# ESP32-S3-M_2_2024-03-15.net
KiCad netlist of a schematic drawn in Altium Designer
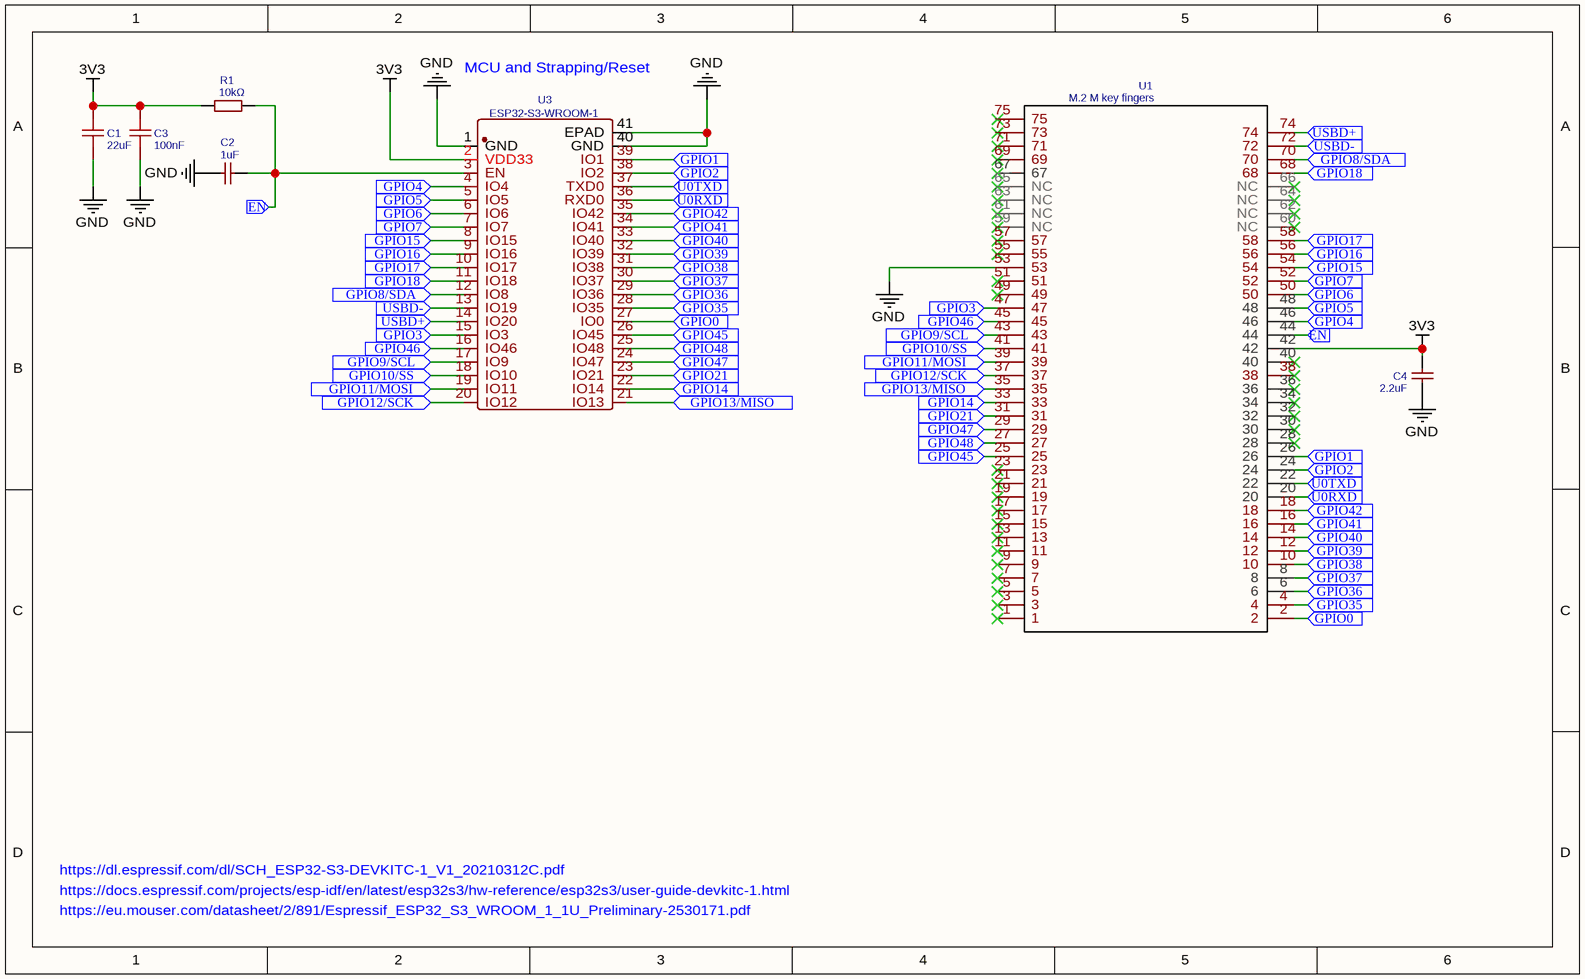
[diagram p0: ESP32-S3-M.2_2024-03-15.schdoc]

(export (version "E")
  (design (tool "Eeschema 10.0.6"))
  (components
    (comp (ref "C1")
      (value "22uF")
      (fields
        (field (name "MANUFACTURER") "SAMSUNG(三星)")
        (field (name "MANUFACTURER PART") "CL10A226MQ8NRNC")
      )
      (libsource (lib "altium-import") (part "root_1_22uF_"))
    )
    (comp (ref "C2")
      (value "1uF")
      (fields
        (field (name "MANUFACTURER PART") "CL10A105KB8NNNC")
        (field (name "MANUFACTURER") "SAMSUNG(三星)")
      )
      (libsource (lib "altium-import") (part "root_0_1uF_"))
    )
    (comp (ref "C3")
      (value "100nF")
      (fields
        (field (name "MANUFACTURER") "YAGEO(国巨)")
        (field (name "MANUFACTURER PART") "CC0603KRX7R9BB104")
      )
      (libsource (lib "altium-import") (part "root_1_100nF_"))
    )
    (comp (ref "C4")
      (value "2.2uF")
      (fields
        (field (name "MANUFACTURER PART") "CL10A225KP8NNNC")
        (field (name "MANUFACTURER") "SAMSUNG(三星)")
      )
      (libsource (lib "altium-import") (part "root_1_2.2uF_"))
    )
    (comp (ref "R1")
      (value "10kΩ")
      (fields (field (name "MANUFACTURER") "YAGEO(国巨)") (field (name "MANUFACTURER PART") "RC0603FR-0710KL"))
      (libsource (lib "altium-import") (part "root_0_10kΩ_"))
    )
    (comp (ref "U1")
      (value "M.2 M key fingers")
      (fields (field (name "CONTRIBUTOR") "Nikola Pantelin"))
      (libsource (lib "altium-import") (part "root_0_M.2 M key fingers_"))
    )
    (comp (ref "U3")
      (value "ESP32-S3-WROOM-1")
      (fields (field (name "MANUFACTURER") "Espressif Systems") (field (name "CONTRIBUTOR") "max30012540"))
      (libsource (lib "altium-import") (part "root_0_ESP32-S3-WROOM-1_"))
    )
  )
  (nets
    (net (code "1") (name "/EN") (class "Default")
      (node (ref "C2") (pin "2") (pinfunction "2_2") (pintype "passive"))
      (node (ref "R1") (pin "2") (pinfunction "2_2") (pintype "passive"))
      (node (ref "U1") (pin "44") (pinfunction "44_44") (pintype "passive"))
      (node (ref "U3") (pin "3") (pinfunction "EN_3") (pintype "passive"))
    )
    (net (code "2") (name "/GPIO0") (class "Default")
      (node (ref "U1") (pin "2") (pinfunction "2_2") (pintype "passive"))
      (node (ref "U3") (pin "27") (pinfunction "IO0_27") (pintype "passive"))
    )
    (net (code "3") (name "/GPIO1") (class "Default")
      (node (ref "U1") (pin "26") (pinfunction "26_26") (pintype "passive"))
      (node (ref "U3") (pin "39") (pinfunction "IO1_39") (pintype "passive"))
    )
    (net (code "4") (name "/GPIO2") (class "Default")
      (node (ref "U1") (pin "24") (pinfunction "24_24") (pintype "passive"))
      (node (ref "U3") (pin "38") (pinfunction "IO2_38") (pintype "passive"))
    )
    (net (code "5") (name "/GPIO3") (class "Default")
      (node (ref "U1") (pin "47") (pinfunction "47_47") (pintype "passive"))
      (node (ref "U3") (pin "15") (pinfunction "IO3_15") (pintype "passive"))
    )
    (net (code "6") (name "/GPIO4") (class "Default")
      (node (ref "U1") (pin "46") (pinfunction "46_46") (pintype "passive"))
      (node (ref "U3") (pin "4") (pinfunction "IO4_4") (pintype "passive"))
    )
    (net (code "7") (name "/GPIO5") (class "Default")
      (node (ref "U1") (pin "48") (pinfunction "48_48") (pintype "passive"))
      (node (ref "U3") (pin "5") (pinfunction "IO5_5") (pintype "passive"))
    )
    (net (code "8") (name "/GPIO6") (class "Default")
      (node (ref "U1") (pin "50") (pinfunction "50_50") (pintype "passive"))
      (node (ref "U3") (pin "6") (pinfunction "IO6_6") (pintype "passive"))
    )
    (net (code "9") (name "/GPIO7") (class "Default")
      (node (ref "U1") (pin "52") (pinfunction "52_52") (pintype "passive"))
      (node (ref "U3") (pin "7") (pinfunction "IO7_7") (pintype "passive"))
    )
    (net (code "10") (name "/GPIO8{slash}SDA") (class "Default")
      (node (ref "U1") (pin "70") (pinfunction "70_70") (pintype "passive"))
      (node (ref "U3") (pin "12") (pinfunction "IO8_12") (pintype "passive"))
    )
    (net (code "11") (name "/GPIO9{slash}SCL") (class "Default")
      (node (ref "U1") (pin "43") (pinfunction "43_43") (pintype "passive"))
      (node (ref "U3") (pin "17") (pinfunction "IO9_17") (pintype "passive"))
    )
    (net (code "12") (name "/GPIO10{slash}SS") (class "Default")
      (node (ref "U1") (pin "41") (pinfunction "41_41") (pintype "passive"))
      (node (ref "U3") (pin "18") (pinfunction "IO10_18") (pintype "passive"))
    )
    (net (code "13") (name "/GPIO11{slash}MOSI") (class "Default")
      (node (ref "U1") (pin "39") (pinfunction "39_39") (pintype "passive"))
      (node (ref "U3") (pin "19") (pinfunction "IO11_19") (pintype "passive"))
    )
    (net (code "14") (name "/GPIO12{slash}SCK") (class "Default")
      (node (ref "U1") (pin "37") (pinfunction "37_37") (pintype "passive"))
      (node (ref "U3") (pin "20") (pinfunction "IO12_20") (pintype "passive"))
    )
    (net (code "15") (name "/GPIO13{slash}MISO") (class "Default")
      (node (ref "U1") (pin "35") (pinfunction "35_35") (pintype "passive"))
      (node (ref "U3") (pin "21") (pinfunction "IO13_21") (pintype "passive"))
    )
    (net (code "16") (name "/GPIO14") (class "Default")
      (node (ref "U1") (pin "33") (pinfunction "33_33") (pintype "passive"))
      (node (ref "U3") (pin "22") (pinfunction "IO14_22") (pintype "passive"))
    )
    (net (code "17") (name "/GPIO15") (class "Default")
      (node (ref "U1") (pin "54") (pinfunction "54_54") (pintype "passive"))
      (node (ref "U3") (pin "8") (pinfunction "IO15_8") (pintype "passive"))
    )
    (net (code "18") (name "/GPIO16") (class "Default")
      (node (ref "U1") (pin "56") (pinfunction "56_56") (pintype "passive"))
      (node (ref "U3") (pin "9") (pinfunction "IO16_9") (pintype "passive"))
    )
    (net (code "19") (name "/GPIO17") (class "Default")
      (node (ref "U1") (pin "58") (pinfunction "58_58") (pintype "passive"))
      (node (ref "U3") (pin "10") (pinfunction "IO17_10") (pintype "passive"))
    )
    (net (code "20") (name "/GPIO18") (class "Default")
      (node (ref "U1") (pin "68") (pinfunction "68_68") (pintype "passive"))
      (node (ref "U3") (pin "11") (pinfunction "IO18_11") (pintype "passive"))
    )
    (net (code "21") (name "/GPIO21") (class "Default")
      (node (ref "U1") (pin "31") (pinfunction "31_31") (pintype "passive"))
      (node (ref "U3") (pin "23") (pinfunction "IO21_23") (pintype "passive"))
    )
    (net (code "22") (name "/GPIO35") (class "Default")
      (node (ref "U1") (pin "4") (pinfunction "4_4") (pintype "passive"))
      (node (ref "U3") (pin "28") (pinfunction "IO35_28") (pintype "passive"))
    )
    (net (code "23") (name "/GPIO36") (class "Default")
      (node (ref "U1") (pin "6") (pinfunction "6_6") (pintype "passive"))
      (node (ref "U3") (pin "29") (pinfunction "IO36_29") (pintype "passive"))
    )
    (net (code "24") (name "/GPIO37") (class "Default")
      (node (ref "U1") (pin "8") (pinfunction "8_8") (pintype "passive"))
      (node (ref "U3") (pin "30") (pinfunction "IO37_30") (pintype "passive"))
    )
    (net (code "25") (name "/GPIO38") (class "Default")
      (node (ref "U1") (pin "10") (pinfunction "10_10") (pintype "passive"))
      (node (ref "U3") (pin "31") (pinfunction "IO38_31") (pintype "passive"))
    )
    (net (code "26") (name "/GPIO39") (class "Default")
      (node (ref "U1") (pin "12") (pinfunction "12_12") (pintype "passive"))
      (node (ref "U3") (pin "32") (pinfunction "IO39_32") (pintype "passive"))
    )
    (net (code "27") (name "/GPIO40") (class "Default")
      (node (ref "U1") (pin "14") (pinfunction "14_14") (pintype "passive"))
      (node (ref "U3") (pin "33") (pinfunction "IO40_33") (pintype "passive"))
    )
    (net (code "28") (name "/GPIO41") (class "Default")
      (node (ref "U1") (pin "16") (pinfunction "16_16") (pintype "passive"))
      (node (ref "U3") (pin "34") (pinfunction "IO41_34") (pintype "passive"))
    )
    (net (code "29") (name "/GPIO42") (class "Default")
      (node (ref "U1") (pin "18") (pinfunction "18_18") (pintype "passive"))
      (node (ref "U3") (pin "35") (pinfunction "IO42_35") (pintype "passive"))
    )
    (net (code "30") (name "/GPIO45") (class "Default")
      (node (ref "U1") (pin "25") (pinfunction "25_25") (pintype "passive"))
      (node (ref "U3") (pin "26") (pinfunction "IO45_26") (pintype "passive"))
    )
    (net (code "31") (name "/GPIO46") (class "Default")
      (node (ref "U1") (pin "45") (pinfunction "45_45") (pintype "passive"))
      (node (ref "U3") (pin "16") (pinfunction "IO46_16") (pintype "passive"))
    )
    (net (code "32") (name "/GPIO47") (class "Default")
      (node (ref "U1") (pin "29") (pinfunction "29_29") (pintype "passive"))
      (node (ref "U3") (pin "24") (pinfunction "IO47_24") (pintype "passive"))
    )
    (net (code "33") (name "/GPIO48") (class "Default")
      (node (ref "U1") (pin "27") (pinfunction "27_27") (pintype "passive"))
      (node (ref "U3") (pin "25") (pinfunction "IO48_25") (pintype "passive"))
    )
    (net (code "34") (name "/U0RXD") (class "Default")
      (node (ref "U1") (pin "20") (pinfunction "20_20") (pintype "passive"))
      (node (ref "U3") (pin "36") (pinfunction "RXD0_36") (pintype "passive"))
    )
    (net (code "35") (name "/U0TXD") (class "Default")
      (node (ref "U1") (pin "22") (pinfunction "22_22") (pintype "passive"))
      (node (ref "U3") (pin "37") (pinfunction "TXD0_37") (pintype "passive"))
    )
    (net (code "36") (name "/USBD+") (class "Default")
      (node (ref "U1") (pin "74") (pinfunction "74_74") (pintype "passive"))
      (node (ref "U3") (pin "14") (pinfunction "IO20_14") (pintype "passive"))
    )
    (net (code "37") (name "/USBD-") (class "Default")
      (node (ref "U1") (pin "72") (pinfunction "72_72") (pintype "passive"))
      (node (ref "U3") (pin "13") (pinfunction "IO19_13") (pintype "passive"))
    )
    (net (code "38") (name "3V3") (class "Default")
      (node (ref "C1") (pin "2") (pinfunction "2_2") (pintype "passive"))
      (node (ref "C3") (pin "2") (pinfunction "2_2") (pintype "passive"))
      (node (ref "C4") (pin "2") (pinfunction "2_2") (pintype "passive"))
      (node (ref "R1") (pin "1") (pinfunction "1_1") (pintype "passive"))
      (node (ref "U1") (pin "42") (pinfunction "42_42") (pintype "passive"))
      (node (ref "U3") (pin "2") (pinfunction "VDD33_2") (pintype "passive"))
    )
    (net (code "39") (name "GND") (class "Default")
      (node (ref "C1") (pin "1") (pinfunction "1_1") (pintype "passive"))
      (node (ref "C2") (pin "1") (pinfunction "1_1") (pintype "passive"))
      (node (ref "C3") (pin "1") (pinfunction "1_1") (pintype "passive"))
      (node (ref "C4") (pin "1") (pinfunction "1_1") (pintype "passive"))
      (node (ref "U1") (pin "53") (pinfunction "53_53") (pintype "passive"))
      (node (ref "U3") (pin "1") (pinfunction "GND_1") (pintype "passive"))
      (node (ref "U3") (pin "40") (pinfunction "GND_40") (pintype "passive"))
      (node (ref "U3") (pin "41") (pinfunction "EPAD_41") (pintype "passive"))
    )
    (net (code "40") (name "unconnected-(U1-NC-Pad59)") (class "Default")
      (node (ref "U1") (pin "59") (pinfunction "NC_59") (pintype "passive+no_connect"))
    )
    (net (code "41") (name "unconnected-(U1-NC-Pad60)") (class "Default")
      (node (ref "U1") (pin "60") (pinfunction "NC_60") (pintype "passive+no_connect"))
    )
    (net (code "42") (name "unconnected-(U1-NC-Pad61)") (class "Default")
      (node (ref "U1") (pin "61") (pinfunction "NC_61") (pintype "passive+no_connect"))
    )
    (net (code "43") (name "unconnected-(U1-NC-Pad62)") (class "Default")
      (node (ref "U1") (pin "62") (pinfunction "NC_62") (pintype "passive+no_connect"))
    )
    (net (code "44") (name "unconnected-(U1-NC-Pad63)") (class "Default")
      (node (ref "U1") (pin "63") (pinfunction "NC_63") (pintype "passive+no_connect"))
    )
    (net (code "45") (name "unconnected-(U1-NC-Pad64)") (class "Default")
      (node (ref "U1") (pin "64") (pinfunction "NC_64") (pintype "passive+no_connect"))
    )
    (net (code "46") (name "unconnected-(U1-NC-Pad65)") (class "Default")
      (node (ref "U1") (pin "65") (pinfunction "NC_65") (pintype "passive+no_connect"))
    )
    (net (code "47") (name "unconnected-(U1-NC-Pad66)") (class "Default")
      (node (ref "U1") (pin "66") (pinfunction "NC_66") (pintype "passive+no_connect"))
    )
    (net (code "48") (name "unconnected-(U1-Pad1)") (class "Default")
      (node (ref "U1") (pin "1") (pinfunction "1_1") (pintype "passive+no_connect"))
    )
    (net (code "49") (name "unconnected-(U1-Pad3)") (class "Default")
      (node (ref "U1") (pin "3") (pinfunction "3_3") (pintype "passive+no_connect"))
    )
    (net (code "50") (name "unconnected-(U1-Pad5)") (class "Default")
      (node (ref "U1") (pin "5") (pinfunction "5_5") (pintype "passive+no_connect"))
    )
    (net (code "51") (name "unconnected-(U1-Pad7)") (class "Default")
      (node (ref "U1") (pin "7") (pinfunction "7_7") (pintype "passive+no_connect"))
    )
    (net (code "52") (name "unconnected-(U1-Pad9)") (class "Default")
      (node (ref "U1") (pin "9") (pinfunction "9_9") (pintype "passive+no_connect"))
    )
    (net (code "53") (name "unconnected-(U1-Pad11)") (class "Default")
      (node (ref "U1") (pin "11") (pinfunction "11_11") (pintype "passive+no_connect"))
    )
    (net (code "54") (name "unconnected-(U1-Pad13)") (class "Default")
      (node (ref "U1") (pin "13") (pinfunction "13_13") (pintype "passive+no_connect"))
    )
    (net (code "55") (name "unconnected-(U1-Pad15)") (class "Default")
      (node (ref "U1") (pin "15") (pinfunction "15_15") (pintype "passive+no_connect"))
    )
    (net (code "56") (name "unconnected-(U1-Pad17)") (class "Default")
      (node (ref "U1") (pin "17") (pinfunction "17_17") (pintype "passive+no_connect"))
    )
    (net (code "57") (name "unconnected-(U1-Pad19)") (class "Default")
      (node (ref "U1") (pin "19") (pinfunction "19_19") (pintype "passive+no_connect"))
    )
    (net (code "58") (name "unconnected-(U1-Pad21)") (class "Default")
      (node (ref "U1") (pin "21") (pinfunction "21_21") (pintype "passive+no_connect"))
    )
    (net (code "59") (name "unconnected-(U1-Pad23)") (class "Default")
      (node (ref "U1") (pin "23") (pinfunction "23_23") (pintype "passive+no_connect"))
    )
    (net (code "60") (name "unconnected-(U1-Pad28)") (class "Default")
      (node (ref "U1") (pin "28") (pinfunction "28_28") (pintype "passive+no_connect"))
    )
    (net (code "61") (name "unconnected-(U1-Pad30)") (class "Default")
      (node (ref "U1") (pin "30") (pinfunction "30_30") (pintype "passive+no_connect"))
    )
    (net (code "62") (name "unconnected-(U1-Pad32)") (class "Default")
      (node (ref "U1") (pin "32") (pinfunction "32_32") (pintype "passive+no_connect"))
    )
    (net (code "63") (name "unconnected-(U1-Pad34)") (class "Default")
      (node (ref "U1") (pin "34") (pinfunction "34_34") (pintype "passive+no_connect"))
    )
    (net (code "64") (name "unconnected-(U1-Pad36)") (class "Default")
      (node (ref "U1") (pin "36") (pinfunction "36_36") (pintype "passive+no_connect"))
    )
    (net (code "65") (name "unconnected-(U1-Pad38)") (class "Default")
      (node (ref "U1") (pin "38") (pinfunction "38_38") (pintype "passive+no_connect"))
    )
    (net (code "66") (name "unconnected-(U1-Pad40)") (class "Default")
      (node (ref "U1") (pin "40") (pinfunction "40_40") (pintype "passive+no_connect"))
    )
    (net (code "67") (name "unconnected-(U1-Pad49)") (class "Default")
      (node (ref "U1") (pin "49") (pinfunction "49_49") (pintype "passive+no_connect"))
    )
    (net (code "68") (name "unconnected-(U1-Pad51)") (class "Default")
      (node (ref "U1") (pin "51") (pinfunction "51_51") (pintype "passive+no_connect"))
    )
    (net (code "69") (name "unconnected-(U1-Pad55)") (class "Default")
      (node (ref "U1") (pin "55") (pinfunction "55_55") (pintype "passive+no_connect"))
    )
    (net (code "70") (name "unconnected-(U1-Pad57)") (class "Default")
      (node (ref "U1") (pin "57") (pinfunction "57_57") (pintype "passive+no_connect"))
    )
    (net (code "71") (name "unconnected-(U1-Pad67)") (class "Default")
      (node (ref "U1") (pin "67") (pinfunction "67_67") (pintype "passive+no_connect"))
    )
    (net (code "72") (name "unconnected-(U1-Pad69)") (class "Default")
      (node (ref "U1") (pin "69") (pinfunction "69_69") (pintype "passive+no_connect"))
    )
    (net (code "73") (name "unconnected-(U1-Pad71)") (class "Default")
      (node (ref "U1") (pin "71") (pinfunction "71_71") (pintype "passive+no_connect"))
    )
    (net (code "74") (name "unconnected-(U1-Pad73)") (class "Default")
      (node (ref "U1") (pin "73") (pinfunction "73_73") (pintype "passive+no_connect"))
    )
    (net (code "75") (name "unconnected-(U1-Pad75)") (class "Default")
      (node (ref "U1") (pin "75") (pinfunction "75_75") (pintype "passive+no_connect"))
    )
  )
)
